# Bus_Definition_V1_21.net
KiCad netlist of a schematic drawn in EAGLE
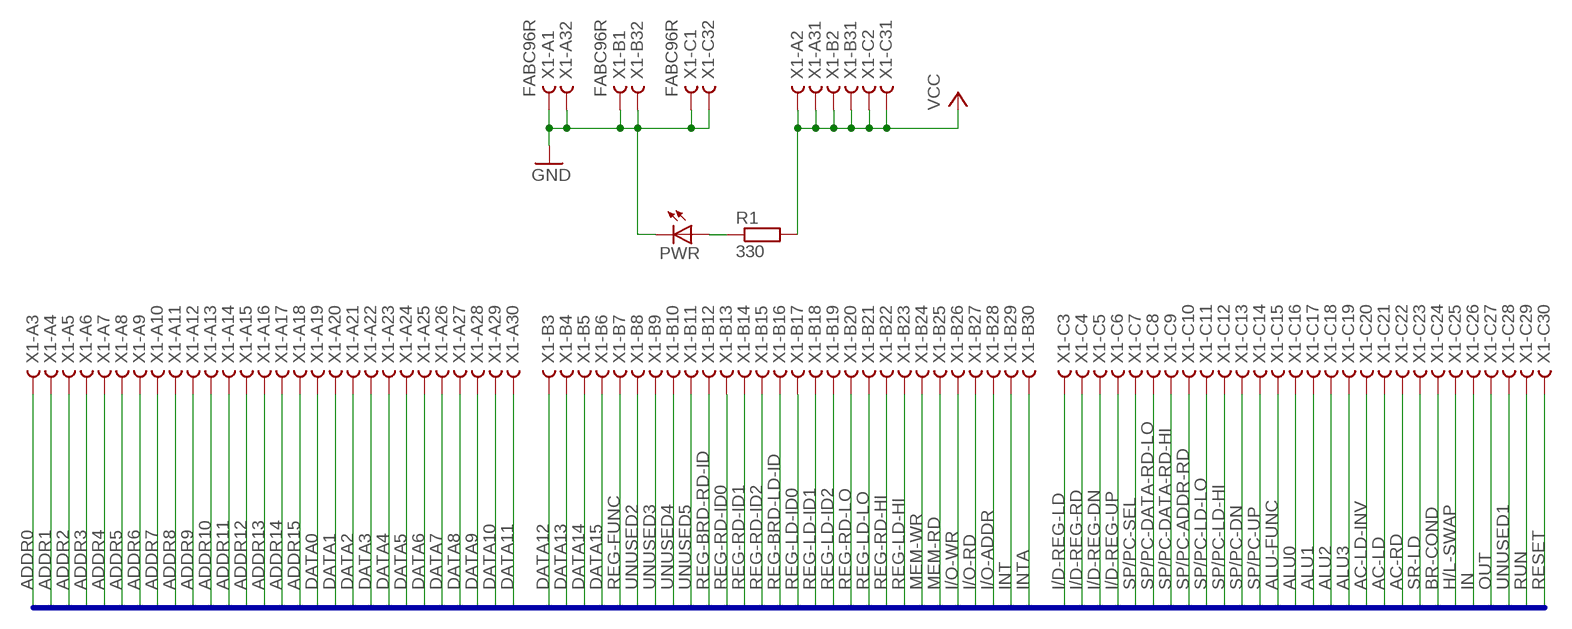
[diagram p0: schematic, sheet 1]

(export (version "E")
  (design (tool "Eeschema 10.0.6"))
  (components
    (comp (ref "PWR")
      (value "LED5MM")
      (footprint "eagle-import:LED5MM")
      (libsource (lib "eagle-import") (part "LED5MM"))
    )
    (comp (ref "R1")
      (value "330")
      (footprint "eagle-import:0207_10")
      (libsource (lib "eagle-import") (part "R0207/10"))
    )
    (comp (ref "X1")
      (value "FABC96R")
      (footprint "eagle-import:FABC96R")
      (libsource (lib "eagle-import") (part "FABC96R"))
    )
  )
  (nets
    (net (code "1") (name "/AC-LD") (class "Default")
      (node (ref "X1") (pin "C21") (pinfunction "B_C21") (pintype "passive"))
    )
    (net (code "2") (name "/AC-LD-INV") (class "Default")
      (node (ref "X1") (pin "C20") (pinfunction "B_C20") (pintype "passive"))
    )
    (net (code "3") (name "/AC-RD") (class "Default")
      (node (ref "X1") (pin "C22") (pinfunction "B_C22") (pintype "passive"))
    )
    (net (code "4") (name "/ADDR0") (class "Default")
      (node (ref "X1") (pin "A3") (pinfunction "B_A3") (pintype "passive"))
    )
    (net (code "5") (name "/ADDR1") (class "Default")
      (node (ref "X1") (pin "A4") (pinfunction "B_A4") (pintype "passive"))
    )
    (net (code "6") (name "/ADDR2") (class "Default")
      (node (ref "X1") (pin "A5") (pinfunction "B_A5") (pintype "passive"))
    )
    (net (code "7") (name "/ADDR3") (class "Default")
      (node (ref "X1") (pin "A6") (pinfunction "B_A6") (pintype "passive"))
    )
    (net (code "8") (name "/ADDR4") (class "Default")
      (node (ref "X1") (pin "A7") (pinfunction "B_A7") (pintype "passive"))
    )
    (net (code "9") (name "/ADDR5") (class "Default")
      (node (ref "X1") (pin "A8") (pinfunction "B_A8") (pintype "passive"))
    )
    (net (code "10") (name "/ADDR6") (class "Default")
      (node (ref "X1") (pin "A9") (pinfunction "B_A9") (pintype "passive"))
    )
    (net (code "11") (name "/ADDR7") (class "Default")
      (node (ref "X1") (pin "A10") (pinfunction "B_A10") (pintype "passive"))
    )
    (net (code "12") (name "/ADDR8") (class "Default")
      (node (ref "X1") (pin "A11") (pinfunction "B_A11") (pintype "passive"))
    )
    (net (code "13") (name "/ADDR9") (class "Default")
      (node (ref "X1") (pin "A12") (pinfunction "B_A12") (pintype "passive"))
    )
    (net (code "14") (name "/ADDR10") (class "Default")
      (node (ref "X1") (pin "A13") (pinfunction "B_A13") (pintype "passive"))
    )
    (net (code "15") (name "/ADDR11") (class "Default")
      (node (ref "X1") (pin "A14") (pinfunction "B_A14") (pintype "passive"))
    )
    (net (code "16") (name "/ADDR12") (class "Default")
      (node (ref "X1") (pin "A15") (pinfunction "B_A15") (pintype "passive"))
    )
    (net (code "17") (name "/ADDR13") (class "Default")
      (node (ref "X1") (pin "A16") (pinfunction "B_A16") (pintype "passive"))
    )
    (net (code "18") (name "/ADDR14") (class "Default")
      (node (ref "X1") (pin "A17") (pinfunction "B_A17") (pintype "passive"))
    )
    (net (code "19") (name "/ADDR15") (class "Default")
      (node (ref "X1") (pin "A18") (pinfunction "B_A18") (pintype "passive"))
    )
    (net (code "20") (name "/ALU-FUNC") (class "Default")
      (node (ref "X1") (pin "C15") (pinfunction "B_C15") (pintype "passive"))
    )
    (net (code "21") (name "/ALU0") (class "Default")
      (node (ref "X1") (pin "C16") (pinfunction "B_C16") (pintype "passive"))
    )
    (net (code "22") (name "/ALU1") (class "Default")
      (node (ref "X1") (pin "C17") (pinfunction "B_C17") (pintype "passive"))
    )
    (net (code "23") (name "/ALU2") (class "Default")
      (node (ref "X1") (pin "C18") (pinfunction "B_C18") (pintype "passive"))
    )
    (net (code "24") (name "/ALU3") (class "Default")
      (node (ref "X1") (pin "C19") (pinfunction "B_C19") (pintype "passive"))
    )
    (net (code "25") (name "/BR-COND") (class "Default")
      (node (ref "X1") (pin "C24") (pinfunction "B_C24") (pintype "passive"))
    )
    (net (code "26") (name "/DATA0") (class "Default")
      (node (ref "X1") (pin "A19") (pinfunction "B_A19") (pintype "passive"))
    )
    (net (code "27") (name "/DATA1") (class "Default")
      (node (ref "X1") (pin "A20") (pinfunction "B_A20") (pintype "passive"))
    )
    (net (code "28") (name "/DATA2") (class "Default")
      (node (ref "X1") (pin "A21") (pinfunction "B_A21") (pintype "passive"))
    )
    (net (code "29") (name "/DATA3") (class "Default")
      (node (ref "X1") (pin "A22") (pinfunction "B_A22") (pintype "passive"))
    )
    (net (code "30") (name "/DATA4") (class "Default")
      (node (ref "X1") (pin "A23") (pinfunction "B_A23") (pintype "passive"))
    )
    (net (code "31") (name "/DATA5") (class "Default")
      (node (ref "X1") (pin "A24") (pinfunction "B_A24") (pintype "passive"))
    )
    (net (code "32") (name "/DATA6") (class "Default")
      (node (ref "X1") (pin "A25") (pinfunction "B_A25") (pintype "passive"))
    )
    (net (code "33") (name "/DATA7") (class "Default")
      (node (ref "X1") (pin "A26") (pinfunction "B_A26") (pintype "passive"))
    )
    (net (code "34") (name "/DATA8") (class "Default")
      (node (ref "X1") (pin "A27") (pinfunction "B_A27") (pintype "passive"))
    )
    (net (code "35") (name "/DATA9") (class "Default")
      (node (ref "X1") (pin "A28") (pinfunction "B_A28") (pintype "passive"))
    )
    (net (code "36") (name "/DATA10") (class "Default")
      (node (ref "X1") (pin "A29") (pinfunction "B_A29") (pintype "passive"))
    )
    (net (code "37") (name "/DATA11") (class "Default")
      (node (ref "X1") (pin "A30") (pinfunction "B_A30") (pintype "passive"))
    )
    (net (code "38") (name "/DATA12") (class "Default")
      (node (ref "X1") (pin "B3") (pinfunction "B_B3") (pintype "passive"))
    )
    (net (code "39") (name "/DATA13") (class "Default")
      (node (ref "X1") (pin "B4") (pinfunction "B_B4") (pintype "passive"))
    )
    (net (code "40") (name "/DATA14") (class "Default")
      (node (ref "X1") (pin "B5") (pinfunction "B_B5") (pintype "passive"))
    )
    (net (code "41") (name "/DATA15") (class "Default")
      (node (ref "X1") (pin "B6") (pinfunction "B_B6") (pintype "passive"))
    )
    (net (code "42") (name "/H{slash}L-SWAP") (class "Default")
      (node (ref "X1") (pin "C25") (pinfunction "B_C25") (pintype "passive"))
    )
    (net (code "43") (name "/IN") (class "Default")
      (node (ref "X1") (pin "C26") (pinfunction "B_C26") (pintype "passive"))
    )
    (net (code "44") (name "/INT") (class "Default")
      (node (ref "X1") (pin "B29") (pinfunction "B_B29") (pintype "passive"))
    )
    (net (code "45") (name "/INTA") (class "Default")
      (node (ref "X1") (pin "B30") (pinfunction "B_B30") (pintype "passive"))
    )
    (net (code "46") (name "/I{slash}D-REG-DN") (class "Default")
      (node (ref "X1") (pin "C5") (pinfunction "B_C5") (pintype "passive"))
    )
    (net (code "47") (name "/I{slash}D-REG-LD") (class "Default")
      (node (ref "X1") (pin "C3") (pinfunction "B_C3") (pintype "passive"))
    )
    (net (code "48") (name "/I{slash}D-REG-RD") (class "Default")
      (node (ref "X1") (pin "C4") (pinfunction "B_C4") (pintype "passive"))
    )
    (net (code "49") (name "/I{slash}D-REG-UP") (class "Default")
      (node (ref "X1") (pin "C6") (pinfunction "B_C6") (pintype "passive"))
    )
    (net (code "50") (name "/I{slash}O-ADDR") (class "Default")
      (node (ref "X1") (pin "B28") (pinfunction "B_B28") (pintype "passive"))
    )
    (net (code "51") (name "/I{slash}O-RD") (class "Default")
      (node (ref "X1") (pin "B27") (pinfunction "B_B27") (pintype "passive"))
    )
    (net (code "52") (name "/I{slash}O-WR") (class "Default")
      (node (ref "X1") (pin "B26") (pinfunction "B_B26") (pintype "passive"))
    )
    (net (code "53") (name "/MEM-RD") (class "Default")
      (node (ref "X1") (pin "B25") (pinfunction "B_B25") (pintype "passive"))
    )
    (net (code "54") (name "/MEM-WR") (class "Default")
      (node (ref "X1") (pin "B24") (pinfunction "B_B24") (pintype "passive"))
    )
    (net (code "55") (name "/OUT") (class "Default")
      (node (ref "X1") (pin "C27") (pinfunction "B_C27") (pintype "passive"))
    )
    (net (code "56") (name "/REG-BRD-LD-ID") (class "Default")
      (node (ref "X1") (pin "B16") (pinfunction "B_B16") (pintype "passive"))
    )
    (net (code "57") (name "/REG-BRD-RD-ID") (class "Default")
      (node (ref "X1") (pin "B12") (pinfunction "B_B12") (pintype "passive"))
    )
    (net (code "58") (name "/REG-FUNC") (class "Default")
      (node (ref "X1") (pin "B7") (pinfunction "B_B7") (pintype "passive"))
    )
    (net (code "59") (name "/REG-LD-HI") (class "Default")
      (node (ref "X1") (pin "B23") (pinfunction "B_B23") (pintype "passive"))
    )
    (net (code "60") (name "/REG-LD-ID0") (class "Default")
      (node (ref "X1") (pin "B17") (pinfunction "B_B17") (pintype "passive"))
    )
    (net (code "61") (name "/REG-LD-ID1") (class "Default")
      (node (ref "X1") (pin "B18") (pinfunction "B_B18") (pintype "passive"))
    )
    (net (code "62") (name "/REG-LD-ID2") (class "Default")
      (node (ref "X1") (pin "B19") (pinfunction "B_B19") (pintype "passive"))
    )
    (net (code "63") (name "/REG-LD-LO") (class "Default")
      (node (ref "X1") (pin "B21") (pinfunction "B_B21") (pintype "passive"))
    )
    (net (code "64") (name "/REG-RD-HI") (class "Default")
      (node (ref "X1") (pin "B22") (pinfunction "B_B22") (pintype "passive"))
    )
    (net (code "65") (name "/REG-RD-ID0") (class "Default")
      (node (ref "X1") (pin "B13") (pinfunction "B_B13") (pintype "passive"))
    )
    (net (code "66") (name "/REG-RD-ID1") (class "Default")
      (node (ref "X1") (pin "B14") (pinfunction "B_B14") (pintype "passive"))
    )
    (net (code "67") (name "/REG-RD-ID2") (class "Default")
      (node (ref "X1") (pin "B15") (pinfunction "B_B15") (pintype "passive"))
    )
    (net (code "68") (name "/REG-RD-LO") (class "Default")
      (node (ref "X1") (pin "B20") (pinfunction "B_B20") (pintype "passive"))
    )
    (net (code "69") (name "/RESET") (class "Default")
      (node (ref "X1") (pin "C30") (pinfunction "B_C30") (pintype "passive"))
    )
    (net (code "70") (name "/RUN") (class "Default")
      (node (ref "X1") (pin "C29") (pinfunction "B_C29") (pintype "passive"))
    )
    (net (code "71") (name "/SP{slash}PC-ADDR-RD") (class "Default")
      (node (ref "X1") (pin "C10") (pinfunction "B_C10") (pintype "passive"))
    )
    (net (code "72") (name "/SP{slash}PC-DATA-RD-HI") (class "Default")
      (node (ref "X1") (pin "C9") (pinfunction "B_C9") (pintype "passive"))
    )
    (net (code "73") (name "/SP{slash}PC-DATA-RD-LO") (class "Default")
      (node (ref "X1") (pin "C8") (pinfunction "B_C8") (pintype "passive"))
    )
    (net (code "74") (name "/SP{slash}PC-DN") (class "Default")
      (node (ref "X1") (pin "C13") (pinfunction "B_C13") (pintype "passive"))
    )
    (net (code "75") (name "/SP{slash}PC-LD-HI") (class "Default")
      (node (ref "X1") (pin "C12") (pinfunction "B_C12") (pintype "passive"))
    )
    (net (code "76") (name "/SP{slash}PC-LD-LO") (class "Default")
      (node (ref "X1") (pin "C11") (pinfunction "B_C11") (pintype "passive"))
    )
    (net (code "77") (name "/SP{slash}PC-SEL") (class "Default")
      (node (ref "X1") (pin "C7") (pinfunction "B_C7") (pintype "passive"))
    )
    (net (code "78") (name "/SP{slash}PC-UP") (class "Default")
      (node (ref "X1") (pin "C14") (pinfunction "B_C14") (pintype "passive"))
    )
    (net (code "79") (name "/SR-LD") (class "Default")
      (node (ref "X1") (pin "C23") (pinfunction "B_C23") (pintype "passive"))
    )
    (net (code "80") (name "/UNUSED1") (class "Default")
      (node (ref "X1") (pin "C28") (pinfunction "B_C28") (pintype "passive"))
    )
    (net (code "81") (name "/UNUSED2") (class "Default")
      (node (ref "X1") (pin "B8") (pinfunction "B_B8") (pintype "passive"))
    )
    (net (code "82") (name "/UNUSED3") (class "Default")
      (node (ref "X1") (pin "B9") (pinfunction "B_B9") (pintype "passive"))
    )
    (net (code "83") (name "/UNUSED4") (class "Default")
      (node (ref "X1") (pin "B10") (pinfunction "B_B10") (pintype "passive"))
    )
    (net (code "84") (name "/UNUSED5") (class "Default")
      (node (ref "X1") (pin "B11") (pinfunction "B_B11") (pintype "passive"))
    )
    (net (code "85") (name "GND") (class "Default")
      (node (ref "PWR") (pin "K") (pinfunction "C_K") (pintype "passive"))
      (node (ref "X1") (pin "A1") (pinfunction "B_A1") (pintype "passive"))
      (node (ref "X1") (pin "A32") (pinfunction "B_A32") (pintype "passive"))
      (node (ref "X1") (pin "B1") (pinfunction "B_B1") (pintype "passive"))
      (node (ref "X1") (pin "B32") (pinfunction "B_B32") (pintype "passive"))
      (node (ref "X1") (pin "C1") (pinfunction "B_C1") (pintype "passive"))
      (node (ref "X1") (pin "C32") (pinfunction "B_C32") (pintype "passive"))
    )
    (net (code "86") (name "Net-(PWR-PadA)") (class "Default")
      (node (ref "PWR") (pin "A") (pinfunction "A_A") (pintype "passive"))
      (node (ref "R1") (pin "1") (pinfunction "1_1") (pintype "passive"))
    )
    (net (code "87") (name "VCC") (class "Default")
      (node (ref "R1") (pin "2") (pinfunction "2_2") (pintype "passive"))
      (node (ref "X1") (pin "A2") (pinfunction "B_A2") (pintype "passive"))
      (node (ref "X1") (pin "A31") (pinfunction "B_A31") (pintype "passive"))
      (node (ref "X1") (pin "B2") (pinfunction "B_B2") (pintype "passive"))
      (node (ref "X1") (pin "B31") (pinfunction "B_B31") (pintype "passive"))
      (node (ref "X1") (pin "C2") (pinfunction "B_C2") (pintype "passive"))
      (node (ref "X1") (pin "C31") (pinfunction "B_C31") (pintype "passive"))
    )
  )
)
